# asset-tracker-v006.net
KiCad netlist of a schematic drawn in EAGLE
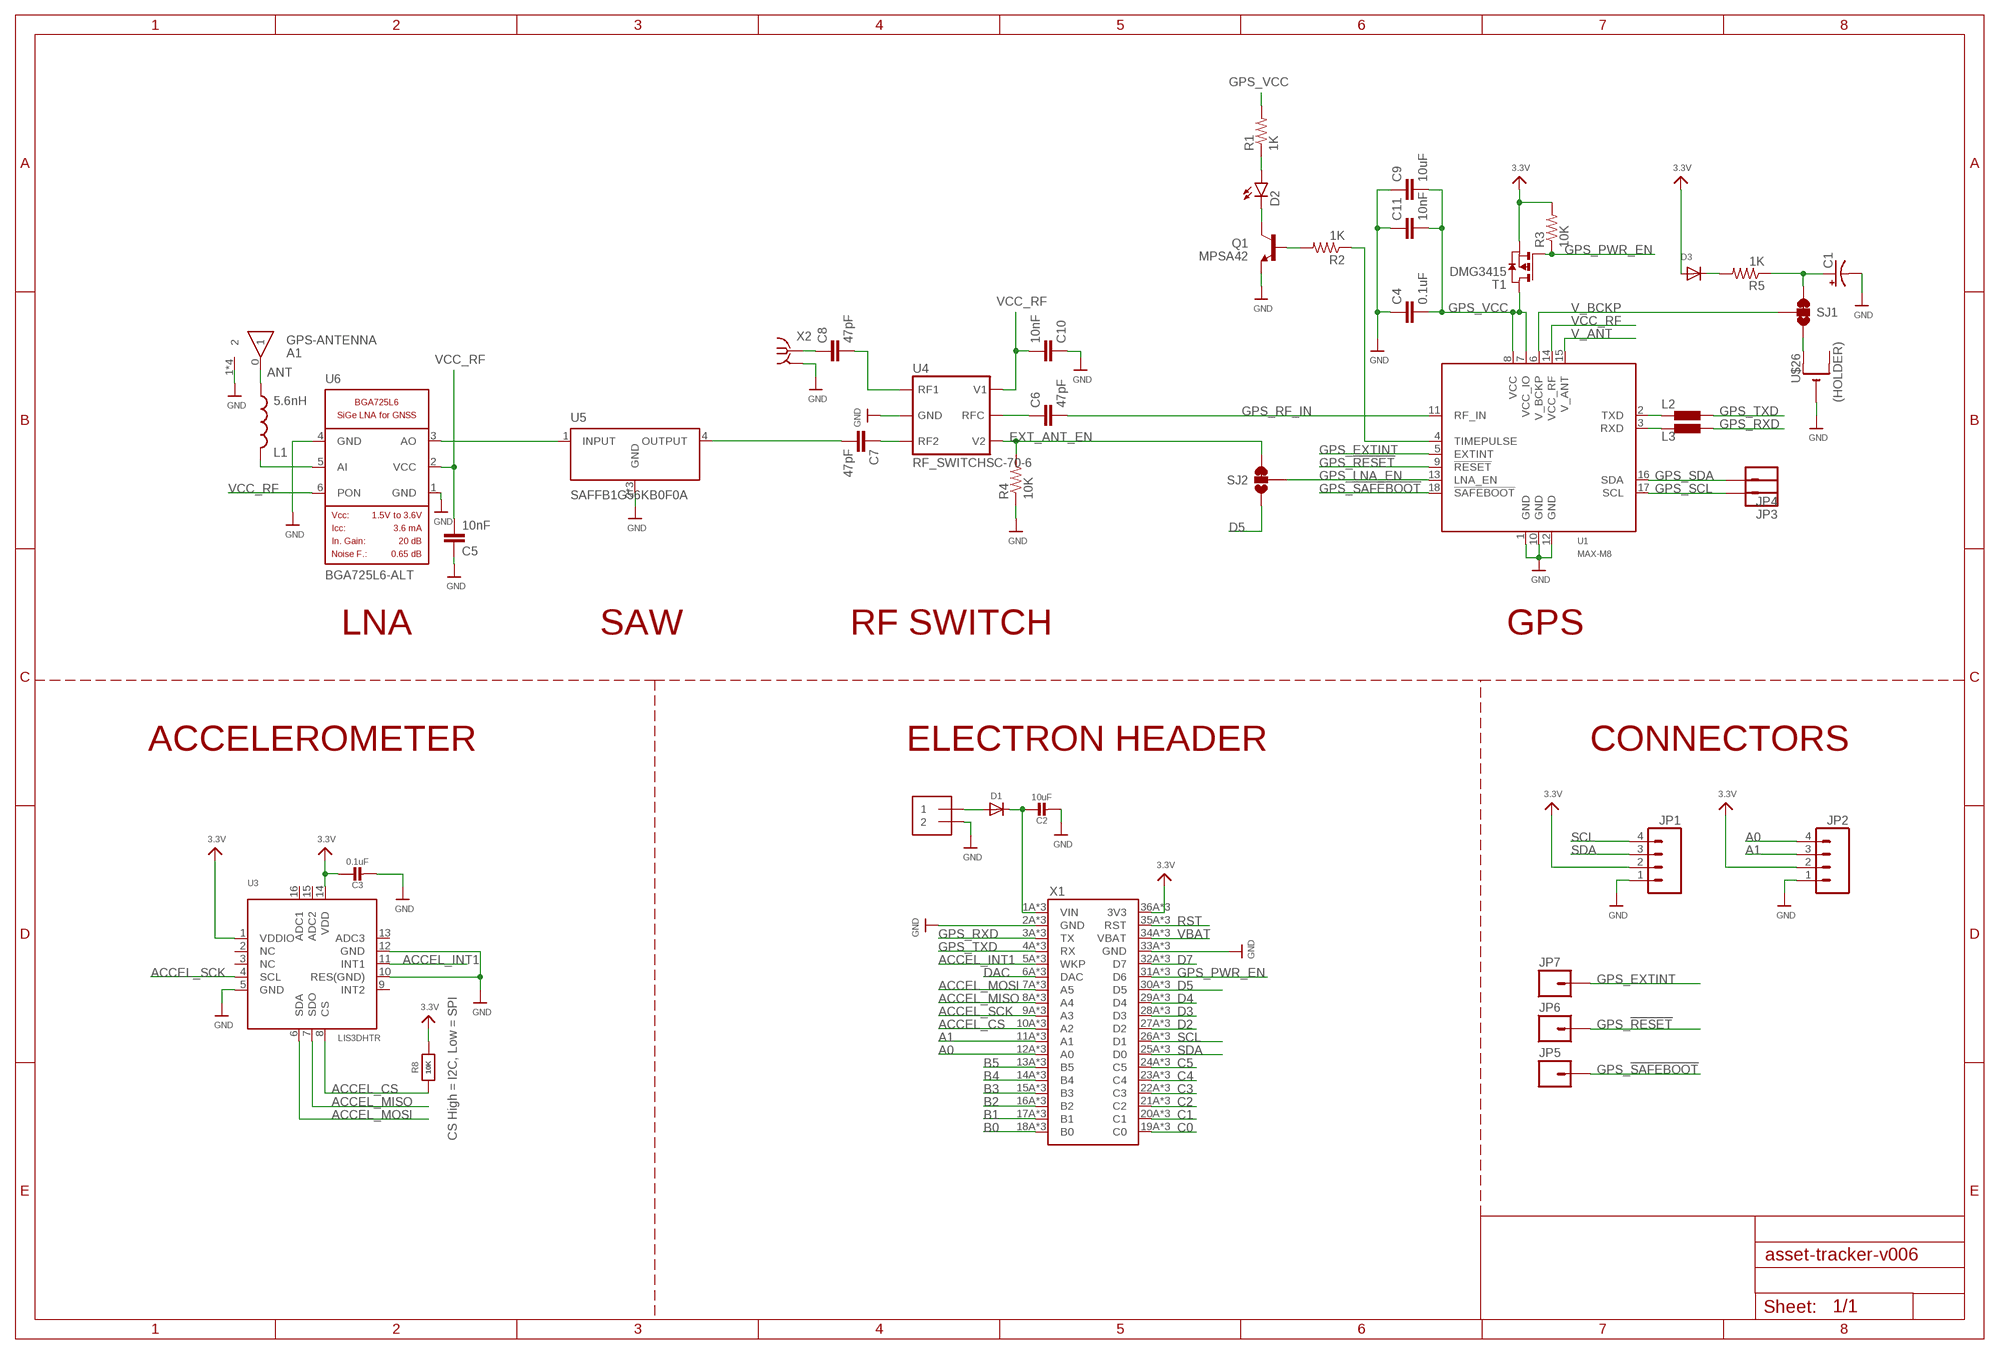
[diagram p0: schematic, sheet 1]

(export (version "E")
  (design (tool "Eeschema 10.0.6"))
  (components
    (comp (ref "A1")
      (value "GPS-ANTENNA")
      (footprint "eagle-import:ANT1818B00BT1516S")
      (libsource (lib "eagle-import") (part "GPS-ANTENNA"))
    )
    (comp (ref "C1")
      (value "SUPERCAP")
      (footprint "eagle-import:414-VA5R")
      (libsource (lib "eagle-import") (part "SUPERCAP"))
    )
    (comp (ref "C2")
      (value "10uF")
      (footprint "eagle-import:_0402MP")
      (libsource (lib "eagle-import") (part "CAP_CERAMIC_0402MP"))
    )
    (comp (ref "C3")
      (value "0.1uF")
      (footprint "eagle-import:_0402MP")
      (libsource (lib "eagle-import") (part "CAP_CERAMIC_0402MP"))
    )
    (comp (ref "C4")
      (value "0.1uF")
      (footprint "eagle-import:C0402")
      (libsource (lib "eagle-import") (part "C-EUC0402"))
    )
    (comp (ref "C5")
      (value "10nF")
      (footprint "eagle-import:C0402")
      (libsource (lib "eagle-import") (part "C-EUC0402"))
    )
    (comp (ref "C6")
      (value "47pF")
      (footprint "eagle-import:C0201")
      (libsource (lib "eagle-import") (part "C-EUC0201"))
    )
    (comp (ref "C7")
      (value "47pF")
      (footprint "eagle-import:C0201")
      (libsource (lib "eagle-import") (part "C-EUC0201"))
    )
    (comp (ref "C8")
      (value "47pF")
      (footprint "eagle-import:C0201")
      (libsource (lib "eagle-import") (part "C-EUC0201"))
    )
    (comp (ref "C9")
      (value "10uF")
      (footprint "eagle-import:C0402")
      (libsource (lib "eagle-import") (part "C-EUC0402"))
    )
    (comp (ref "C10")
      (value "10nF")
      (footprint "eagle-import:C0402")
      (libsource (lib "eagle-import") (part "C-EUC0402"))
    )
    (comp (ref "C11")
      (value "10nF")
      (footprint "eagle-import:C0402")
      (libsource (lib "eagle-import") (part "C-EUC0402"))
    )
    (comp (ref "D1")
      (value "DIODESMA")
      (footprint "eagle-import:SMADIODE")
      (libsource (lib "eagle-import") (part "microbuilder_DIODESMA"))
    )
    (comp (ref "D2")
      (value "LED0603")
      (footprint "eagle-import:LED-0603")
      (libsource (lib "eagle-import") (part "LED0603"))
    )
    (comp (ref "D3")
      (value "DIODESOD-523")
      (footprint "eagle-import:SOD-523")
      (libsource (lib "eagle-import") (part "DIODESOD-523"))
    )
    (comp (ref "J1")
      (value "1X2-3.5MM")
      (footprint "eagle-import:1X2-3.5MM")
      (libsource (lib "eagle-import") (part "1X2-3.5MM"))
    )
    (comp (ref "JP1")
      (value "M04JST-PTH-VERT")
      (footprint "eagle-import:JST-4-PTH-VERT")
      (libsource (lib "eagle-import") (part "M04JST-PTH-VERT"))
    )
    (comp (ref "JP2")
      (value "M04JST-PTH-VERT")
      (footprint "eagle-import:JST-4-PTH-VERT")
      (libsource (lib "eagle-import") (part "M04JST-PTH-VERT"))
    )
    (comp (ref "JP3")
      (value "M01SMD-4.5X1.5")
      (footprint "eagle-import:PAD-1.5X4.5")
      (libsource (lib "eagle-import") (part "M01SMD-4.5X1.5"))
    )
    (comp (ref "JP4")
      (value "M01SMD-4.5X1.5")
      (footprint "eagle-import:PAD-1.5X4.5")
      (libsource (lib "eagle-import") (part "M01SMD-4.5X1.5"))
    )
    (comp (ref "JP5")
      (value "M01SMD-4.5X1.5")
      (footprint "eagle-import:PAD-1.5X4.5")
      (libsource (lib "eagle-import") (part "M01SMD-4.5X1.5"))
    )
    (comp (ref "JP6")
      (value "M01SMD-4.5X1.5")
      (footprint "eagle-import:PAD-1.5X4.5")
      (libsource (lib "eagle-import") (part "M01SMD-4.5X1.5"))
    )
    (comp (ref "JP7")
      (value "M01SMD-4.5X1.5")
      (footprint "eagle-import:PAD-1.5X4.5")
      (libsource (lib "eagle-import") (part "M01SMD-4.5X1.5"))
    )
    (comp (ref "L1")
      (value "5.6nH")
      (footprint "eagle-import:C0402")
      (libsource (lib "eagle-import") (part "INDUCTOR0402"))
    )
    (comp (ref "L2")
      (value "BLM15HD102SN1")
      (footprint "eagle-import:0402")
      (libsource (lib "eagle-import") (part "BLM15HD102SN1"))
    )
    (comp (ref "L3")
      (value "BLM15HD102SN1")
      (footprint "eagle-import:0402")
      (libsource (lib "eagle-import") (part "BLM15HD102SN1"))
    )
    (comp (ref "Q1")
      (value "MPSA42")
      (footprint "eagle-import:SOT23-3")
      (libsource (lib "eagle-import") (part "TRANSISTOR_NPNMPSA42"))
    )
    (comp (ref "R1")
      (value "1K")
      (footprint "eagle-import:R0402")
      (libsource (lib "eagle-import") (part "R-US_R0402"))
    )
    (comp (ref "R2")
      (value "1K")
      (footprint "eagle-import:R0402")
      (libsource (lib "eagle-import") (part "R-US_R0402"))
    )
    (comp (ref "R3")
      (value "10K")
      (footprint "eagle-import:R0402")
      (libsource (lib "eagle-import") (part "R-US_R0402"))
    )
    (comp (ref "R4")
      (value "10K")
      (footprint "eagle-import:R0402")
      (libsource (lib "eagle-import") (part "R-US_R0402"))
    )
    (comp (ref "R5")
      (value "1K")
      (footprint "eagle-import:R0402")
      (libsource (lib "eagle-import") (part "R-US_R0402"))
    )
    (comp (ref "R8")
      (value "10K")
      (footprint "eagle-import:_0402MP")
      (libsource (lib "eagle-import") (part "RESISTOR_0402MP"))
    )
    (comp (ref "SJ1")
      (value "JUMPER-PAD-3-2OF3_NC_BY_TRACE_LARGE")
      (footprint "eagle-import:PAD-JUMPER-3-2OF3_NC_BY_TRACE_YES_SILK_LARGE")
      (libsource (lib "eagle-import") (part "JUMPER-PAD-3-2OF3_NC_BY_TRACE_LARGE"))
    )
    (comp (ref "SJ2")
      (value "JUMPER-PAD-3-2OF3_NC_BY_TRACE_LARGE")
      (footprint "eagle-import:PAD-JUMPER-3-2OF3_NC_BY_TRACE_YES_SILK_LARGE")
      (libsource (lib "eagle-import") (part "JUMPER-PAD-3-2OF3_NC_BY_TRACE_LARGE"))
    )
    (comp (ref "T1")
      (value "DMG3415")
      (footprint "eagle-import:SOT-23")
      (libsource (lib "eagle-import") (part "PMOSSOT23"))
    )
    (comp (ref "U$26")
      (value "CR2032SMT")
      (footprint "eagle-import:CR2032-SMD")
      (libsource (lib "eagle-import") (part "CR2032SMT"))
    )
    (comp (ref "U1")
      (value "MAX-M8")
      (footprint "eagle-import:MAX-M8")
      (libsource (lib "eagle-import") (part "MAX-M8"))
    )
    (comp (ref "U3")
      (value "LIS3DHTR")
      (footprint "eagle-import:LGA16_3X3MM")
      (libsource (lib "eagle-import") (part "ACCEL_LIS3DHTR"))
    )
    (comp (ref "U4")
      (value "RF_SWITCHSC-70-6")
      (footprint "eagle-import:SC70-6")
      (libsource (lib "eagle-import") (part "RF_SWITCHSC-70-6"))
    )
    (comp (ref "U5")
      (value "SAFFB1G56KB0F0A")
      (footprint "eagle-import:QCS5I")
      (libsource (lib "eagle-import") (part "FILTERS"))
    )
    (comp (ref "U6")
      (value "BGA725L6-ALT")
      (footprint "eagle-import:LNA-TSLP-6-2-ALT")
      (libsource (lib "eagle-import") (part "BGA725L6-ALT"))
    )
    (comp (ref "X1")
      (value "ELECTRON")
      (footprint "eagle-import:ELECTRON_SMT")
      (libsource (lib "eagle-import") (part "ELECTRON_SMT"))
    )
    (comp (ref "X2")
      (value "IPEX-20279-001E")
      (footprint "eagle-import:IPEX-20279-001E")
      (libsource (lib "eagle-import") (part "IPEX-20279-001E"))
    )
  )
  (nets
    (net (code "1") (name "/A0") (class "Default")
      (node (ref "JP2") (pin "4") (pinfunction "4_4") (pintype "passive"))
      (node (ref "X1") (pin "12A") (pinfunction "A0_12A") (pintype "bidirectional"))
      (node (ref "X1") (pin "12B") (pinfunction "A0_12B") (pintype "bidirectional"))
      (node (ref "X1") (pin "12C") (pinfunction "A0_12C") (pintype "bidirectional"))
    )
    (net (code "2") (name "/A1") (class "Default")
      (node (ref "JP2") (pin "3") (pinfunction "3_3") (pintype "passive"))
      (node (ref "X1") (pin "11A") (pinfunction "A1_11A") (pintype "bidirectional"))
      (node (ref "X1") (pin "11B") (pinfunction "A1_11B") (pintype "bidirectional"))
      (node (ref "X1") (pin "11C") (pinfunction "A1_11C") (pintype "bidirectional"))
    )
    (net (code "3") (name "/ACCEL_CS") (class "Default")
      (node (ref "R8") (pin "1") (pinfunction "1_1") (pintype "passive"))
      (node (ref "U3") (pin "8") (pinfunction "CS_8") (pintype "input"))
      (node (ref "X1") (pin "10A") (pinfunction "A2_10A") (pintype "bidirectional"))
      (node (ref "X1") (pin "10B") (pinfunction "A2_10B") (pintype "bidirectional"))
      (node (ref "X1") (pin "10C") (pinfunction "A2_10C") (pintype "bidirectional"))
    )
    (net (code "4") (name "/ACCEL_INT1") (class "Default")
      (node (ref "U3") (pin "11") (pinfunction "INT1_11") (pintype "output"))
      (node (ref "X1") (pin "5A") (pinfunction "WKP_5A") (pintype "bidirectional"))
      (node (ref "X1") (pin "5B") (pinfunction "WKP_5B") (pintype "bidirectional"))
      (node (ref "X1") (pin "5C") (pinfunction "WKP_5C") (pintype "bidirectional"))
    )
    (net (code "5") (name "/ACCEL_MISO") (class "Default")
      (node (ref "U3") (pin "7") (pinfunction "SDO_7") (pintype "bidirectional"))
      (node (ref "X1") (pin "8A") (pinfunction "A4_8A") (pintype "bidirectional"))
      (node (ref "X1") (pin "8B") (pinfunction "A4_8B") (pintype "bidirectional"))
      (node (ref "X1") (pin "8C") (pinfunction "A4_8C") (pintype "bidirectional"))
    )
    (net (code "6") (name "/ACCEL_MOSI") (class "Default")
      (node (ref "U3") (pin "6") (pinfunction "SDA_6") (pintype "bidirectional"))
      (node (ref "X1") (pin "7A") (pinfunction "A5_7A") (pintype "bidirectional"))
      (node (ref "X1") (pin "7B") (pinfunction "A5_7B") (pintype "bidirectional"))
      (node (ref "X1") (pin "7C") (pinfunction "A5_7C") (pintype "bidirectional"))
    )
    (net (code "7") (name "/ACCEL_SCK") (class "Default")
      (node (ref "U3") (pin "4") (pinfunction "SCL_4") (pintype "bidirectional"))
      (node (ref "X1") (pin "9A") (pinfunction "A3_9A") (pintype "bidirectional"))
      (node (ref "X1") (pin "9B") (pinfunction "A3_9B") (pintype "bidirectional"))
      (node (ref "X1") (pin "9C") (pinfunction "A3_9C") (pintype "bidirectional"))
    )
    (net (code "8") (name "/ANT") (class "Default")
      (node (ref "A1") (pin "0") (pinfunction "1_0") (pintype "output"))
      (node (ref "L1") (pin "2") (pinfunction "2_2") (pintype "passive"))
    )
    (net (code "9") (name "/B0") (class "Default")
      (node (ref "X1") (pin "18A") (pinfunction "B0_18A") (pintype "bidirectional"))
      (node (ref "X1") (pin "18B") (pinfunction "B0_18B") (pintype "bidirectional"))
      (node (ref "X1") (pin "18C") (pinfunction "B0_18C") (pintype "bidirectional"))
    )
    (net (code "10") (name "/B1") (class "Default")
      (node (ref "X1") (pin "17A") (pinfunction "B1_17A") (pintype "bidirectional"))
      (node (ref "X1") (pin "17B") (pinfunction "B1_17B") (pintype "bidirectional"))
      (node (ref "X1") (pin "17C") (pinfunction "B1_17C") (pintype "bidirectional"))
    )
    (net (code "11") (name "/B2") (class "Default")
      (node (ref "X1") (pin "16A") (pinfunction "B2_16A") (pintype "bidirectional"))
      (node (ref "X1") (pin "16B") (pinfunction "B2_16B") (pintype "bidirectional"))
      (node (ref "X1") (pin "16C") (pinfunction "B2_16C") (pintype "bidirectional"))
    )
    (net (code "12") (name "/B3") (class "Default")
      (node (ref "X1") (pin "15A") (pinfunction "B3_15A") (pintype "bidirectional"))
      (node (ref "X1") (pin "15B") (pinfunction "B3_15B") (pintype "bidirectional"))
      (node (ref "X1") (pin "15C") (pinfunction "B3_15C") (pintype "bidirectional"))
    )
    (net (code "13") (name "/B4") (class "Default")
      (node (ref "X1") (pin "14A") (pinfunction "B4_14A") (pintype "bidirectional"))
      (node (ref "X1") (pin "14B") (pinfunction "B4_14B") (pintype "bidirectional"))
      (node (ref "X1") (pin "14C") (pinfunction "B4_14C") (pintype "bidirectional"))
    )
    (net (code "14") (name "/B5") (class "Default")
      (node (ref "X1") (pin "13A") (pinfunction "B5_13A") (pintype "bidirectional"))
      (node (ref "X1") (pin "13B") (pinfunction "B5_13B") (pintype "bidirectional"))
      (node (ref "X1") (pin "13C") (pinfunction "B5_13C") (pintype "bidirectional"))
    )
    (net (code "15") (name "/C0") (class "Default")
      (node (ref "X1") (pin "19A") (pinfunction "C0_19A") (pintype "bidirectional"))
      (node (ref "X1") (pin "19B") (pinfunction "C0_19B") (pintype "bidirectional"))
      (node (ref "X1") (pin "19C") (pinfunction "C0_19C") (pintype "bidirectional"))
    )
    (net (code "16") (name "/C1") (class "Default")
      (node (ref "X1") (pin "20A") (pinfunction "C1_20A") (pintype "bidirectional"))
      (node (ref "X1") (pin "20B") (pinfunction "C1_20B") (pintype "bidirectional"))
      (node (ref "X1") (pin "20C") (pinfunction "C1_20C") (pintype "bidirectional"))
    )
    (net (code "17") (name "/C2") (class "Default")
      (node (ref "X1") (pin "21A") (pinfunction "C2_21A") (pintype "bidirectional"))
      (node (ref "X1") (pin "21B") (pinfunction "C2_21B") (pintype "bidirectional"))
      (node (ref "X1") (pin "21C") (pinfunction "C2_21C") (pintype "bidirectional"))
    )
    (net (code "18") (name "/C3") (class "Default")
      (node (ref "X1") (pin "22A") (pinfunction "C3_22A") (pintype "bidirectional"))
      (node (ref "X1") (pin "22B") (pinfunction "C3_22B") (pintype "bidirectional"))
      (node (ref "X1") (pin "22C") (pinfunction "C3_22C") (pintype "bidirectional"))
    )
    (net (code "19") (name "/C4") (class "Default")
      (node (ref "X1") (pin "23A") (pinfunction "C4_23A") (pintype "bidirectional"))
      (node (ref "X1") (pin "23B") (pinfunction "C4_23B") (pintype "bidirectional"))
      (node (ref "X1") (pin "23C") (pinfunction "C4_23C") (pintype "bidirectional"))
    )
    (net (code "20") (name "/C5") (class "Default")
      (node (ref "X1") (pin "24A") (pinfunction "C5_24A") (pintype "bidirectional"))
      (node (ref "X1") (pin "24B") (pinfunction "C5_24B") (pintype "bidirectional"))
      (node (ref "X1") (pin "24C") (pinfunction "C5_24C") (pintype "bidirectional"))
    )
    (net (code "21") (name "/D2") (class "Default")
      (node (ref "X1") (pin "27A") (pinfunction "D2_27A") (pintype "bidirectional"))
      (node (ref "X1") (pin "27B") (pinfunction "D2_27B") (pintype "bidirectional"))
      (node (ref "X1") (pin "27C") (pinfunction "D2_27C") (pintype "bidirectional"))
    )
    (net (code "22") (name "/D3") (class "Default")
      (node (ref "X1") (pin "28A") (pinfunction "D3_28A") (pintype "bidirectional"))
      (node (ref "X1") (pin "28B") (pinfunction "D3_28B") (pintype "bidirectional"))
      (node (ref "X1") (pin "28C") (pinfunction "D3_28C") (pintype "bidirectional"))
    )
    (net (code "23") (name "/D4") (class "Default")
      (node (ref "X1") (pin "29A") (pinfunction "D4_29A") (pintype "bidirectional"))
      (node (ref "X1") (pin "29B") (pinfunction "D4_29B") (pintype "bidirectional"))
      (node (ref "X1") (pin "29C") (pinfunction "D4_29C") (pintype "bidirectional"))
    )
    (net (code "24") (name "/D5") (class "Default")
      (node (ref "SJ2") (pin "1") (pinfunction "1_1") (pintype "passive"))
      (node (ref "X1") (pin "30A") (pinfunction "D5_30A") (pintype "bidirectional"))
      (node (ref "X1") (pin "30B") (pinfunction "D5_30B") (pintype "bidirectional"))
      (node (ref "X1") (pin "30C") (pinfunction "D5_30C") (pintype "bidirectional"))
    )
    (net (code "25") (name "/D7") (class "Default")
      (node (ref "X1") (pin "32A") (pinfunction "D7_32A") (pintype "bidirectional"))
      (node (ref "X1") (pin "32B") (pinfunction "D7_32B") (pintype "bidirectional"))
      (node (ref "X1") (pin "32C") (pinfunction "D7_32C") (pintype "bidirectional"))
    )
    (net (code "26") (name "/DAC") (class "Default")
      (node (ref "X1") (pin "6A") (pinfunction "DAC_6A") (pintype "bidirectional"))
      (node (ref "X1") (pin "6B") (pinfunction "DAC_6B") (pintype "bidirectional"))
      (node (ref "X1") (pin "6C") (pinfunction "DAC_6C") (pintype "bidirectional"))
    )
    (net (code "27") (name "/EXT_ANT_EN") (class "Default")
      (node (ref "R4") (pin "2") (pinfunction "2_2") (pintype "passive"))
      (node (ref "SJ2") (pin "3") (pinfunction "3_3") (pintype "passive"))
      (node (ref "U4") (pin "4") (pinfunction "V2_4") (pintype "input"))
    )
    (net (code "28") (name "/GPS_EXTINT") (class "Default")
      (node (ref "JP7") (pin "P$1") (pinfunction "1_P$1") (pintype "passive"))
      (node (ref "U1") (pin "5") (pinfunction "EXTINT_5") (pintype "bidirectional"))
    )
    (net (code "29") (name "/GPS_LNA_EN") (class "Default")
      (node (ref "SJ2") (pin "2") (pinfunction "2_2") (pintype "passive"))
      (node (ref "U1") (pin "13") (pinfunction "LNA_EN_13") (pintype "bidirectional"))
    )
    (net (code "30") (name "/GPS_PWR_EN") (class "Default")
      (node (ref "R3") (pin "1") (pinfunction "1_1") (pintype "passive"))
      (node (ref "T1") (pin "3") (pinfunction "G_3") (pintype "passive"))
      (node (ref "X1") (pin "31A") (pinfunction "D6_31A") (pintype "bidirectional"))
      (node (ref "X1") (pin "31B") (pinfunction "D6_31B") (pintype "bidirectional"))
      (node (ref "X1") (pin "31C") (pinfunction "D6_31C") (pintype "bidirectional"))
    )
    (net (code "31") (name "/GPS_RF_IN") (class "Default")
      (node (ref "C6") (pin "2") (pinfunction "2_2") (pintype "passive"))
      (node (ref "U1") (pin "11") (pinfunction "RF_IN_11") (pintype "bidirectional"))
    )
    (net (code "32") (name "/GPS_RXD") (class "Default")
      (node (ref "L3") (pin "2") (pinfunction "2_2") (pintype "passive"))
      (node (ref "X1") (pin "3A") (pinfunction "TX_3A") (pintype "bidirectional"))
      (node (ref "X1") (pin "3B") (pinfunction "TX_3B") (pintype "bidirectional"))
      (node (ref "X1") (pin "3C") (pinfunction "TX_3C") (pintype "bidirectional"))
    )
    (net (code "33") (name "/GPS_SCL") (class "Default")
      (node (ref "JP3") (pin "P$1") (pinfunction "1_P$1") (pintype "passive"))
      (node (ref "U1") (pin "17") (pinfunction "SCL_17") (pintype "bidirectional"))
    )
    (net (code "34") (name "/GPS_SDA") (class "Default")
      (node (ref "JP4") (pin "P$1") (pinfunction "1_P$1") (pintype "passive"))
      (node (ref "U1") (pin "16") (pinfunction "SDA_16") (pintype "bidirectional"))
    )
    (net (code "35") (name "/GPS_TXD") (class "Default")
      (node (ref "L2") (pin "2") (pinfunction "2_2") (pintype "passive"))
      (node (ref "X1") (pin "4A") (pinfunction "RX_4A") (pintype "bidirectional"))
      (node (ref "X1") (pin "4B") (pinfunction "RX_4B") (pintype "bidirectional"))
      (node (ref "X1") (pin "4C") (pinfunction "RX_4C") (pintype "bidirectional"))
    )
    (net (code "36") (name "/GPS_VCC") (class "Default")
      (node (ref "C11") (pin "2") (pinfunction "2_2") (pintype "passive"))
      (node (ref "C4") (pin "2") (pinfunction "2_2") (pintype "passive"))
      (node (ref "C9") (pin "2") (pinfunction "2_2") (pintype "passive"))
      (node (ref "R1") (pin "2") (pinfunction "2_2") (pintype "passive"))
      (node (ref "T1") (pin "1") (pinfunction "D_1") (pintype "passive"))
      (node (ref "U1") (pin "7") (pinfunction "VCC_IO_7") (pintype "bidirectional"))
      (node (ref "U1") (pin "8") (pinfunction "VCC_8") (pintype "bidirectional"))
    )
    (net (code "37") (name "/GPS_~{RESET}") (class "Default")
      (node (ref "JP6") (pin "P$1") (pinfunction "1_P$1") (pintype "passive"))
      (node (ref "U1") (pin "9") (pinfunction "~{RESET}_9") (pintype "bidirectional"))
    )
    (net (code "38") (name "/GPS_~{SAFEBOOT}") (class "Default")
      (node (ref "JP5") (pin "P$1") (pinfunction "1_P$1") (pintype "passive"))
      (node (ref "U1") (pin "18") (pinfunction "~{SAFEBOOT}_18") (pintype "bidirectional"))
    )
    (net (code "39") (name "/RST") (class "Default")
      (node (ref "X1") (pin "35A") (pinfunction "RST_35A") (pintype "bidirectional"))
      (node (ref "X1") (pin "35B") (pinfunction "RST_35B") (pintype "bidirectional"))
      (node (ref "X1") (pin "35C") (pinfunction "RST_35C") (pintype "bidirectional"))
    )
    (net (code "40") (name "/SCL") (class "Default")
      (node (ref "JP1") (pin "4") (pinfunction "4_4") (pintype "passive"))
      (node (ref "X1") (pin "26A") (pinfunction "D1_26A") (pintype "bidirectional"))
      (node (ref "X1") (pin "26B") (pinfunction "D1_26B") (pintype "bidirectional"))
      (node (ref "X1") (pin "26C") (pinfunction "D1_26C") (pintype "bidirectional"))
    )
    (net (code "41") (name "/SDA") (class "Default")
      (node (ref "JP1") (pin "3") (pinfunction "3_3") (pintype "passive"))
      (node (ref "X1") (pin "25A") (pinfunction "D0_25A") (pintype "bidirectional"))
      (node (ref "X1") (pin "25B") (pinfunction "D0_25B") (pintype "bidirectional"))
      (node (ref "X1") (pin "25C") (pinfunction "D0_25C") (pintype "bidirectional"))
    )
    (net (code "42") (name "/VBAT") (class "Default")
      (node (ref "X1") (pin "34A") (pinfunction "VBAT_34A") (pintype "passive"))
      (node (ref "X1") (pin "34B") (pinfunction "VBAT_34B") (pintype "passive"))
      (node (ref "X1") (pin "34C") (pinfunction "VBAT_34C") (pintype "passive"))
    )
    (net (code "43") (name "/VCC_RF") (class "Default")
      (node (ref "C10") (pin "2") (pinfunction "2_2") (pintype "passive"))
      (node (ref "C5") (pin "2") (pinfunction "2_2") (pintype "passive"))
      (node (ref "U1") (pin "14") (pinfunction "VCC_RF_14") (pintype "bidirectional"))
      (node (ref "U4") (pin "6") (pinfunction "V1_6") (pintype "input"))
      (node (ref "U6") (pin "2") (pinfunction "VCC_2") (pintype "power_in"))
      (node (ref "U6") (pin "6") (pinfunction "PON_6") (pintype "input"))
    )
    (net (code "44") (name "/V_ANT") (class "Default")
      (node (ref "U1") (pin "15") (pinfunction "V_ANT_15") (pintype "bidirectional"))
    )
    (net (code "45") (name "/V_BCKP") (class "Default")
      (node (ref "SJ1") (pin "2") (pinfunction "2_2") (pintype "passive"))
      (node (ref "U1") (pin "6") (pinfunction "V_BCKP_6") (pintype "bidirectional"))
    )
    (net (code "46") (name "3.3V") (class "Default")
      (node (ref "C3") (pin "1") (pinfunction "1_1") (pintype "passive"))
      (node (ref "D3") (pin "A") (pinfunction "A_A") (pintype "passive"))
      (node (ref "JP1") (pin "2") (pinfunction "2_2") (pintype "passive"))
      (node (ref "JP2") (pin "2") (pinfunction "2_2") (pintype "passive"))
      (node (ref "R3") (pin "2") (pinfunction "2_2") (pintype "passive"))
      (node (ref "R8") (pin "2") (pinfunction "2_2") (pintype "passive"))
      (node (ref "T1") (pin "2") (pinfunction "S_2") (pintype "passive"))
      (node (ref "U3") (pin "1") (pinfunction "VDDIO_1") (pintype "power_in"))
      (node (ref "U3") (pin "14") (pinfunction "VDD_14") (pintype "power_in"))
      (node (ref "X1") (pin "36A") (pinfunction "3V3_36A") (pintype "power_in"))
      (node (ref "X1") (pin "36B") (pinfunction "3V3_36B") (pintype "power_in"))
      (node (ref "X1") (pin "36C") (pinfunction "3V3_36C") (pintype "power_in"))
    )
    (net (code "47") (name "GND") (class "Default")
      (node (ref "A1") (pin "1") (pinfunction "2_1") (pintype "power_in"))
      (node (ref "A1") (pin "2") (pinfunction "2_2") (pintype "power_in"))
      (node (ref "A1") (pin "3") (pinfunction "2_3") (pintype "power_in"))
      (node (ref "A1") (pin "4") (pinfunction "2_4") (pintype "power_in"))
      (node (ref "C1") (pin "-") (pinfunction "-_-") (pintype "passive"))
      (node (ref "C10") (pin "1") (pinfunction "1_1") (pintype "passive"))
      (node (ref "C11") (pin "1") (pinfunction "1_1") (pintype "passive"))
      (node (ref "C2") (pin "2") (pinfunction "2_2") (pintype "passive"))
      (node (ref "C3") (pin "2") (pinfunction "2_2") (pintype "passive"))
      (node (ref "C4") (pin "1") (pinfunction "1_1") (pintype "passive"))
      (node (ref "C5") (pin "1") (pinfunction "1_1") (pintype "passive"))
      (node (ref "C9") (pin "1") (pinfunction "1_1") (pintype "passive"))
      (node (ref "J1") (pin "2") (pinfunction "2_2") (pintype "passive"))
      (node (ref "JP1") (pin "1") (pinfunction "1_1") (pintype "passive"))
      (node (ref "JP2") (pin "1") (pinfunction "1_1") (pintype "passive"))
      (node (ref "Q1") (pin "2") (pinfunction "E_2") (pintype "passive"))
      (node (ref "R4") (pin "1") (pinfunction "1_1") (pintype "passive"))
      (node (ref "U$26") (pin "-") (pinfunction "-_-") (pintype "passive"))
      (node (ref "U1") (pin "1") (pinfunction "GND_1") (pintype "bidirectional"))
      (node (ref "U1") (pin "10") (pinfunction "GND_10") (pintype "bidirectional"))
      (node (ref "U1") (pin "12") (pinfunction "GND_12") (pintype "bidirectional"))
      (node (ref "U3") (pin "10") (pinfunction "RES(GND)_10") (pintype "bidirectional"))
      (node (ref "U3") (pin "12") (pinfunction "GND_12") (pintype "power_in"))
      (node (ref "U3") (pin "5") (pinfunction "GND_5") (pintype "power_in"))
      (node (ref "U4") (pin "2") (pinfunction "GND_2") (pintype "power_in"))
      (node (ref "U5") (pin "2") (pinfunction "GND_2") (pintype "power_in"))
      (node (ref "U5") (pin "3") (pinfunction "GND_3") (pintype "power_in"))
      (node (ref "U5") (pin "5") (pinfunction "GND_5") (pintype "power_in"))
      (node (ref "U6") (pin "1") (pinfunction "GND_1") (pintype "power_in"))
      (node (ref "U6") (pin "4") (pinfunction "GND_4") (pintype "power_in"))
      (node (ref "X1") (pin "2A") (pinfunction "GND_2A") (pintype "power_in"))
      (node (ref "X1") (pin "2B") (pinfunction "GND_2B") (pintype "power_in"))
      (node (ref "X1") (pin "2C") (pinfunction "GND_2C") (pintype "power_in"))
      (node (ref "X1") (pin "33A") (pinfunction "GND_33A") (pintype "power_in"))
      (node (ref "X1") (pin "33B") (pinfunction "GND_33B") (pintype "power_in"))
      (node (ref "X1") (pin "33C") (pinfunction "GND_33C") (pintype "power_in"))
      (node (ref "X2") (pin "2@1") (pinfunction "GND_2@1") (pintype "passive"))
      (node (ref "X2") (pin "2@2") (pinfunction "GND_2@2") (pintype "passive"))
    )
    (net (code "48") (name "Net-(C1-Pad+)") (class "Default")
      (node (ref "C1") (pin "+") (pinfunction "+_+") (pintype "passive"))
      (node (ref "R5") (pin "1") (pinfunction "1_1") (pintype "passive"))
      (node (ref "SJ1") (pin "3") (pinfunction "3_3") (pintype "passive"))
    )
    (net (code "49") (name "Net-(C2-Pad1)") (class "Default")
      (node (ref "C2") (pin "1") (pinfunction "1_1") (pintype "passive"))
      (node (ref "D1") (pin "C") (pinfunction "C_C") (pintype "passive"))
      (node (ref "X1") (pin "1A") (pinfunction "VIN_1A") (pintype "power_in"))
      (node (ref "X1") (pin "1B") (pinfunction "VIN_1B") (pintype "power_in"))
      (node (ref "X1") (pin "1C") (pinfunction "VIN_1C") (pintype "power_in"))
    )
    (net (code "50") (name "Net-(C8-Pad1)") (class "Default")
      (node (ref "C8") (pin "1") (pinfunction "1_1") (pintype "passive"))
      (node (ref "X2") (pin "1") (pinfunction "1_1") (pintype "passive"))
    )
    (net (code "51") (name "Net-(D1-PadA)") (class "Default")
      (node (ref "D1") (pin "A") (pinfunction "A_A") (pintype "passive"))
      (node (ref "J1") (pin "1") (pinfunction "1_1") (pintype "passive"))
    )
    (net (code "52") (name "Net-(D2-PadA)") (class "Default")
      (node (ref "D2") (pin "A") (pinfunction "A_A") (pintype "passive"))
      (node (ref "R1") (pin "1") (pinfunction "1_1") (pintype "passive"))
    )
    (net (code "53") (name "Net-(D3-C)") (class "Default")
      (node (ref "D3") (pin "K") (pinfunction "C_K") (pintype "passive"))
      (node (ref "R5") (pin "2") (pinfunction "2_2") (pintype "passive"))
    )
    (net (code "54") (name "Net-(Q1-B)") (class "Default")
      (node (ref "Q1") (pin "1") (pinfunction "B_1") (pintype "passive"))
      (node (ref "R2") (pin "2") (pinfunction "2_2") (pintype "passive"))
    )
    (net (code "55") (name "Net-(Q1-C)") (class "Default")
      (node (ref "D2") (pin "C") (pinfunction "C_C") (pintype "passive"))
      (node (ref "Q1") (pin "3") (pinfunction "C_3") (pintype "passive"))
    )
    (net (code "56") (name "Net-(U$26-+)") (class "Default")
      (node (ref "SJ1") (pin "1") (pinfunction "1_1") (pintype "passive"))
      (node (ref "U$26") (pin "+$1") (pinfunction "+_+$1") (pintype "passive"))
    )
    (net (code "57") (name "Net-(U1-RXD)") (class "Default")
      (node (ref "L3") (pin "1") (pinfunction "1_1") (pintype "passive"))
      (node (ref "U1") (pin "3") (pinfunction "RXD_3") (pintype "bidirectional"))
    )
    (net (code "58") (name "Net-(U1-TIMEPULSE)") (class "Default")
      (node (ref "R2") (pin "1") (pinfunction "1_1") (pintype "passive"))
      (node (ref "U1") (pin "4") (pinfunction "TIMEPULSE_4") (pintype "bidirectional"))
    )
    (net (code "59") (name "Net-(U1-TXD)") (class "Default")
      (node (ref "L2") (pin "1") (pinfunction "1_1") (pintype "passive"))
      (node (ref "U1") (pin "2") (pinfunction "TXD_2") (pintype "bidirectional"))
    )
    (net (code "60") (name "Net-(U4-RF1)") (class "Default")
      (node (ref "C8") (pin "2") (pinfunction "2_2") (pintype "passive"))
      (node (ref "U4") (pin "1") (pinfunction "RF1_1") (pintype "output"))
    )
    (net (code "61") (name "Net-(U4-RF2)") (class "Default")
      (node (ref "C7") (pin "1") (pinfunction "1_1") (pintype "passive"))
      (node (ref "U4") (pin "3") (pinfunction "RF2_3") (pintype "output"))
    )
    (net (code "62") (name "Net-(U4-RFC)") (class "Default")
      (node (ref "C6") (pin "1") (pinfunction "1_1") (pintype "passive"))
      (node (ref "U4") (pin "5") (pinfunction "RFC_5") (pintype "input"))
    )
    (net (code "63") (name "Net-(U5-INPUT)") (class "Default")
      (node (ref "U5") (pin "1") (pinfunction "INPUT_1") (pintype "input"))
      (node (ref "U6") (pin "3") (pinfunction "AO_3") (pintype "output"))
    )
    (net (code "64") (name "Net-(U5-OUTPUT)") (class "Default")
      (node (ref "C7") (pin "2") (pinfunction "2_2") (pintype "passive"))
      (node (ref "U5") (pin "4") (pinfunction "OUTPUT_4") (pintype "bidirectional"))
    )
    (net (code "65") (name "Net-(U6-AI)") (class "Default")
      (node (ref "L1") (pin "1") (pinfunction "1_1") (pintype "passive"))
      (node (ref "U6") (pin "5") (pinfunction "AI_5") (pintype "input"))
    )
    (net (code "66") (name "unconnected-(U$26-+1-Pad+$2)") (class "Default")
      (node (ref "U$26") (pin "+$2") (pinfunction "+1_+$2") (pintype "passive"))
    )
    (net (code "67") (name "unconnected-(U3-ADC1-Pad16)") (class "Default")
      (node (ref "U3") (pin "16") (pinfunction "ADC1_16") (pintype "input"))
    )
    (net (code "68") (name "unconnected-(U3-ADC2-Pad15)") (class "Default")
      (node (ref "U3") (pin "15") (pinfunction "ADC2_15") (pintype "input"))
    )
    (net (code "69") (name "unconnected-(U3-ADC3-Pad13)") (class "Default")
      (node (ref "U3") (pin "13") (pinfunction "ADC3_13") (pintype "input"))
    )
    (net (code "70") (name "unconnected-(U3-INT2-Pad9)") (class "Default")
      (node (ref "U3") (pin "9") (pinfunction "INT2_9") (pintype "output"))
    )
    (net (code "71") (name "unconnected-(U3-NC-Pad2)") (class "Default")
      (node (ref "U3") (pin "2") (pinfunction "NC_2") (pintype "no_connect"))
    )
    (net (code "72") (name "unconnected-(U3-NC-Pad3)") (class "Default")
      (node (ref "U3") (pin "3") (pinfunction "NC_3") (pintype "no_connect"))
    )
  )
)
